# 1-Schematic_CJ4_Electrical_Panel.net
KiCad netlist of a schematic drawn in EasyEDA
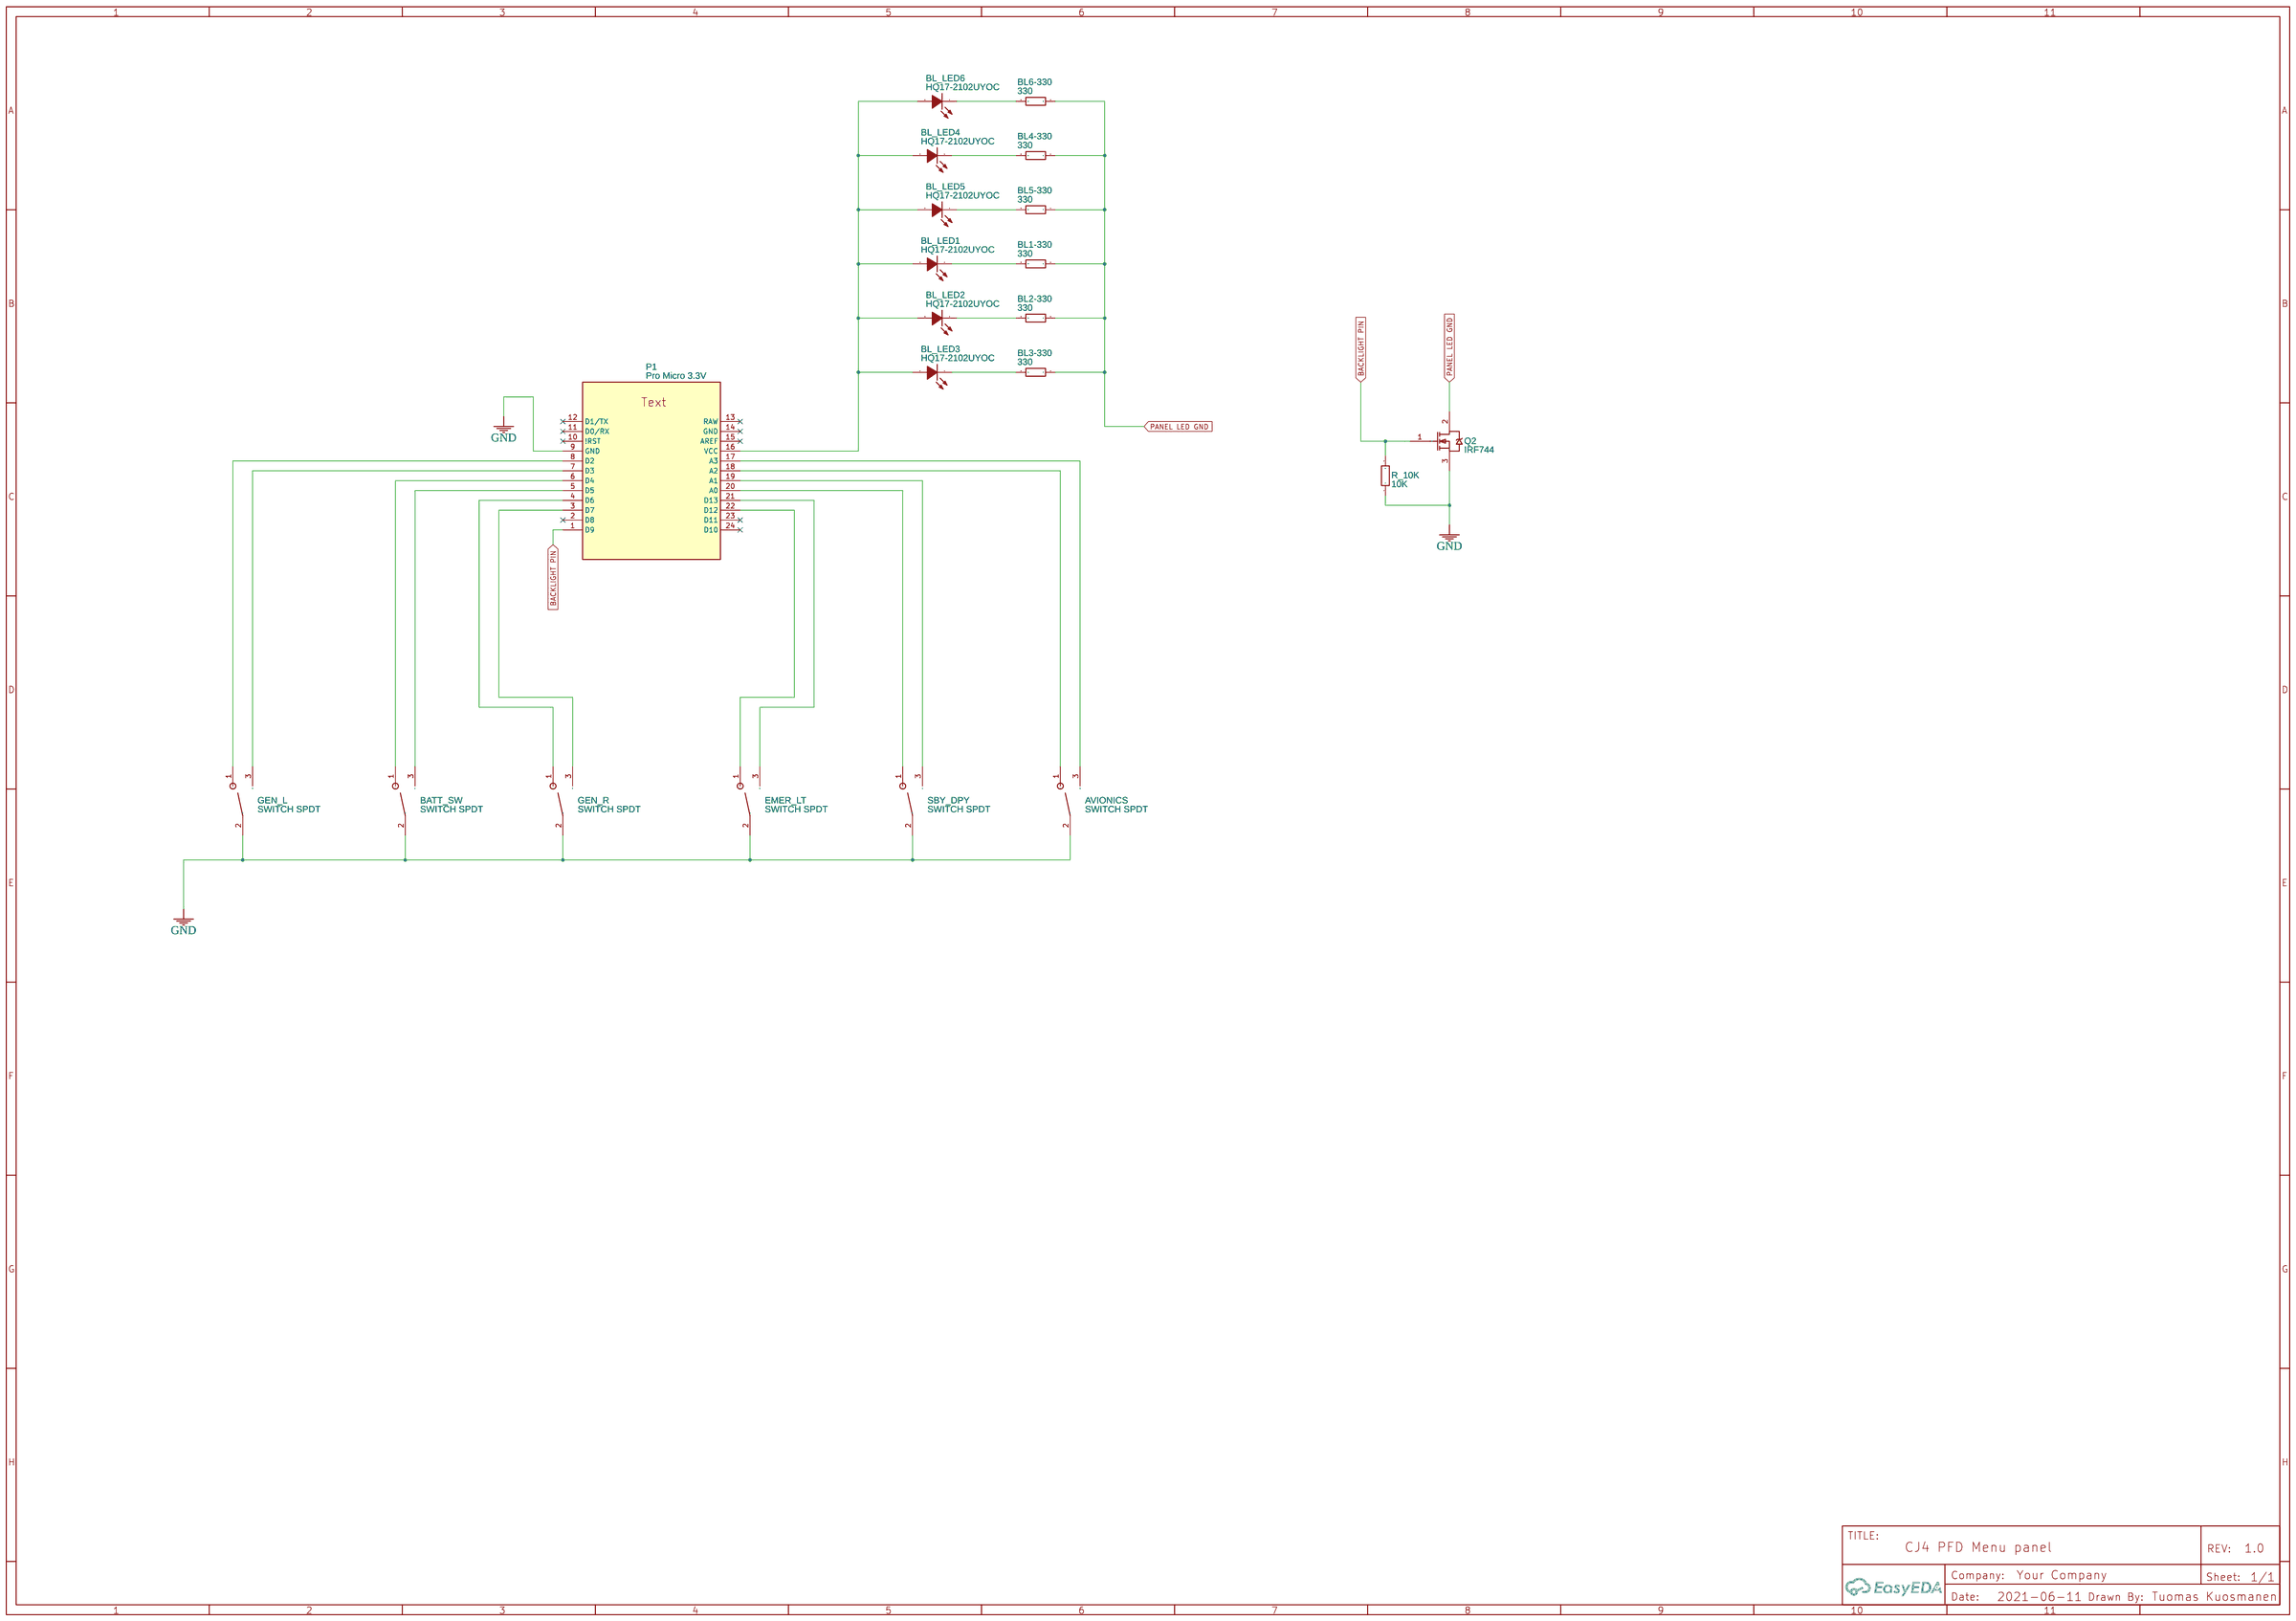
[diagram p0: schematic sheet]

(export (version "E")
  (design (tool "Eeschema 10.0.6"))
  (components
    (comp (ref "AVIONICS")
      (value "SWITCH SPDT")
      (fields
        (field (name "BOM_Manufacturer Part") "200MSP1T1B1M2QEH")
        (field (name "BOM_Supplier Part") "C273365")
      )
      (libsource (lib "") (part "SWITCH SPDT_3"))
    )
    (comp (ref "BATT_SW")
      (value "SWITCH SPDT")
      (fields
        (field (name "BOM_Manufacturer Part") "200MSP1T1B1M2QEH")
        (field (name "BOM_Supplier Part") "C273365")
      )
      (libsource (lib "") (part "SWITCH SPDT_4"))
    )
    (comp (ref "BL1-330")
      (value "330")
      (fields
        (field (name "BOM_Manufacturer Part") "1206W4J0331T5E")
        (field (name "BOM_Supplier Part") "C25374")
      )
      (libsource (lib "") (part "1206W4J0331T5E_3"))
    )
    (comp (ref "BL2-330")
      (value "330")
      (fields
        (field (name "BOM_Manufacturer Part") "1206W4J0331T5E")
        (field (name "BOM_Supplier Part") "C25374")
      )
      (libsource (lib "") (part "1206W4J0331T5E_4"))
    )
    (comp (ref "BL3-330")
      (value "330")
      (fields
        (field (name "BOM_Manufacturer Part") "1206W4J0331T5E")
        (field (name "BOM_Supplier Part") "C25374")
      )
      (libsource (lib "") (part "1206W4J0331T5E_6"))
    )
    (comp (ref "BL4-330")
      (value "330")
      (fields
        (field (name "BOM_Manufacturer Part") "1206W4J0331T5E")
        (field (name "BOM_Supplier Part") "C25374")
      )
      (libsource (lib "") (part "1206W4J0331T5E"))
    )
    (comp (ref "BL5-330")
      (value "330")
      (fields
        (field (name "BOM_Manufacturer Part") "1206W4J0331T5E")
        (field (name "BOM_Supplier Part") "C25374")
      )
      (libsource (lib "") (part "1206W4J0331T5E_1"))
    )
    (comp (ref "BL6-330")
      (value "330")
      (fields
        (field (name "BOM_Manufacturer Part") "1206W4J0331T5E")
        (field (name "BOM_Supplier Part") "C25374")
      )
      (libsource (lib "") (part "1206W4J0331T5E_5"))
    )
    (comp (ref "BL_LED1")
      (value "HQ17-2102UYOC")
      (fields (field (name "BOM_Supplier Part") "C154481"))
      (libsource (lib "") (part "HQ17-2102UYOC"))
    )
    (comp (ref "BL_LED2")
      (value "HQ17-2102UYOC")
      (fields (field (name "BOM_Supplier Part") "C154481"))
      (libsource (lib "") (part "HQ17-2102UYOC"))
    )
    (comp (ref "BL_LED3")
      (value "HQ17-2102UYOC")
      (fields (field (name "BOM_Supplier Part") "C154481"))
      (libsource (lib "") (part "HQ17-2102UYOC"))
    )
    (comp (ref "BL_LED4")
      (value "HQ17-2102UYOC")
      (fields (field (name "BOM_Supplier Part") "C154481"))
      (libsource (lib "") (part "HQ17-2102UYOC"))
    )
    (comp (ref "BL_LED5")
      (value "HQ17-2102UYOC")
      (fields (field (name "BOM_Supplier Part") "C154481"))
      (libsource (lib "") (part "HQ17-2102UYOC"))
    )
    (comp (ref "BL_LED6")
      (value "HQ17-2102UYOC")
      (fields (field (name "BOM_Supplier Part") "C154481"))
      (libsource (lib "") (part "HQ17-2102UYOC"))
    )
    (comp (ref "EMER_LT")
      (value "SWITCH SPDT")
      (fields
        (field (name "BOM_Manufacturer Part") "200MSP1T1B1M2QEH")
        (field (name "BOM_Supplier Part") "C273365")
      )
      (libsource (lib "") (part "SWITCH SPDT_5"))
    )
    (comp (ref "GEN_L")
      (value "SWITCH SPDT")
      (fields
        (field (name "BOM_Manufacturer Part") "200MSP1T1B1M2QEH")
        (field (name "BOM_Supplier Part") "C273365")
      )
      (libsource (lib "") (part "SWITCH SPDT_2"))
    )
    (comp (ref "GEN_R")
      (value "SWITCH SPDT")
      (fields
        (field (name "BOM_Manufacturer Part") "200MSP1T1B1M2QEH")
        (field (name "BOM_Supplier Part") "C273365")
      )
      (libsource (lib "") (part "SWITCH SPDT_1"))
    )
    (comp (ref "P1")
      (value "Pro Micro 3.3V")
      (fields (field (name "BOM_Supplier Part") "12587"))
      (libsource (lib "") (part "Pro Micro 3.3V"))
    )
    (comp (ref "Q2") (value "IRF744") (libsource (lib "") (part "IRF744")))
    (comp (ref "R_10K")
      (value "10K")
      (fields
        (field (name "BOM_Manufacturer Part") "1206W4J0331T5E")
        (field (name "BOM_Supplier Part") "C25374")
      )
      (libsource (lib "") (part "1206W4J0331T5E_2"))
    )
    (comp (ref "SBY_DPY")
      (value "SWITCH SPDT")
      (fields
        (field (name "BOM_Manufacturer Part") "200MSP1T1B1M2QEH")
        (field (name "BOM_Supplier Part") "C273365")
      )
      (libsource (lib "") (part "SWITCH SPDT"))
    )
  )
  (nets
    (net (code "1") (name "BACKLIGHT PIN") (class "Default")
      (node (ref "P1") (pin "1") (pinfunction "D9_1") (pintype "unspecified"))
      (node (ref "Q2") (pin "1") (pinfunction "G_1") (pintype "unspecified"))
      (node (ref "R_10K") (pin "2") (pinfunction "2_2") (pintype "input"))
    )
    (net (code "2") (name "GND") (class "Default")
      (node (ref "AVIONICS") (pin "2") (pinfunction "2_2") (pintype "input"))
      (node (ref "BATT_SW") (pin "2") (pinfunction "2_2") (pintype "input"))
      (node (ref "EMER_LT") (pin "2") (pinfunction "2_2") (pintype "input"))
      (node (ref "GEN_L") (pin "2") (pinfunction "2_2") (pintype "input"))
      (node (ref "GEN_R") (pin "2") (pinfunction "2_2") (pintype "input"))
      (node (ref "P1") (pin "9") (pinfunction "GND_9") (pintype "unspecified"))
      (node (ref "Q2") (pin "3") (pinfunction "S_3") (pintype "unspecified"))
      (node (ref "R_10K") (pin "1") (pinfunction "1_1") (pintype "input"))
      (node (ref "SBY_DPY") (pin "2") (pinfunction "2_2") (pintype "input"))
    )
    (net (code "3") (name "Net-(BL_LED1-A)") (class "Default")
      (node (ref "BL_LED1") (pin "2") (pinfunction "A_2") (pintype "unspecified"))
      (node (ref "BL_LED2") (pin "2") (pinfunction "A_2") (pintype "unspecified"))
      (node (ref "BL_LED3") (pin "2") (pinfunction "A_2") (pintype "unspecified"))
      (node (ref "BL_LED4") (pin "2") (pinfunction "A_2") (pintype "unspecified"))
      (node (ref "BL_LED5") (pin "2") (pinfunction "A_2") (pintype "unspecified"))
      (node (ref "BL_LED6") (pin "2") (pinfunction "A_2") (pintype "unspecified"))
      (node (ref "P1") (pin "16") (pinfunction "VCC_16") (pintype "unspecified"))
    )
    (net (code "4") (name "Net-(BL_LED1-K)") (class "Default")
      (node (ref "BL1-330") (pin "2") (pinfunction "2_2") (pintype "input"))
      (node (ref "BL_LED1") (pin "1") (pinfunction "K_1") (pintype "unspecified"))
    )
    (net (code "5") (name "Net-(BL_LED2-K)") (class "Default")
      (node (ref "BL2-330") (pin "2") (pinfunction "2_2") (pintype "input"))
      (node (ref "BL_LED2") (pin "1") (pinfunction "K_1") (pintype "unspecified"))
    )
    (net (code "6") (name "Net-(BL_LED3-K)") (class "Default")
      (node (ref "BL3-330") (pin "2") (pinfunction "2_2") (pintype "input"))
      (node (ref "BL_LED3") (pin "1") (pinfunction "K_1") (pintype "unspecified"))
    )
    (net (code "7") (name "Net-(BL_LED4-K)") (class "Default")
      (node (ref "BL4-330") (pin "2") (pinfunction "2_2") (pintype "input"))
      (node (ref "BL_LED4") (pin "1") (pinfunction "K_1") (pintype "unspecified"))
    )
    (net (code "8") (name "Net-(BL_LED5-K)") (class "Default")
      (node (ref "BL5-330") (pin "2") (pinfunction "2_2") (pintype "input"))
      (node (ref "BL_LED5") (pin "1") (pinfunction "K_1") (pintype "unspecified"))
    )
    (net (code "9") (name "Net-(BL_LED6-K)") (class "Default")
      (node (ref "BL6-330") (pin "2") (pinfunction "2_2") (pintype "input"))
      (node (ref "BL_LED6") (pin "1") (pinfunction "K_1") (pintype "unspecified"))
    )
    (net (code "10") (name "Net-(P1-A0)") (class "Default")
      (node (ref "P1") (pin "20") (pinfunction "A0_20") (pintype "unspecified"))
      (node (ref "SBY_DPY") (pin "1") (pinfunction "1_1") (pintype "input"))
    )
    (net (code "11") (name "Net-(P1-A1)") (class "Default")
      (node (ref "P1") (pin "19") (pinfunction "A1_19") (pintype "unspecified"))
      (node (ref "SBY_DPY") (pin "3") (pinfunction "3_3") (pintype "input"))
    )
    (net (code "12") (name "Net-(P1-A2)") (class "Default")
      (node (ref "AVIONICS") (pin "1") (pinfunction "1_1") (pintype "input"))
      (node (ref "P1") (pin "18") (pinfunction "A2_18") (pintype "unspecified"))
    )
    (net (code "13") (name "Net-(P1-A3)") (class "Default")
      (node (ref "AVIONICS") (pin "3") (pinfunction "3_3") (pintype "input"))
      (node (ref "P1") (pin "17") (pinfunction "A3_17") (pintype "unspecified"))
    )
    (net (code "14") (name "Net-(P1-D2)") (class "Default")
      (node (ref "GEN_L") (pin "1") (pinfunction "1_1") (pintype "input"))
      (node (ref "P1") (pin "8") (pinfunction "D2_8") (pintype "unspecified"))
    )
    (net (code "15") (name "Net-(P1-D3)") (class "Default")
      (node (ref "GEN_L") (pin "3") (pinfunction "3_3") (pintype "input"))
      (node (ref "P1") (pin "7") (pinfunction "D3_7") (pintype "unspecified"))
    )
    (net (code "16") (name "Net-(P1-D4)") (class "Default")
      (node (ref "BATT_SW") (pin "1") (pinfunction "1_1") (pintype "input"))
      (node (ref "P1") (pin "6") (pinfunction "D4_6") (pintype "unspecified"))
    )
    (net (code "17") (name "Net-(P1-D5)") (class "Default")
      (node (ref "BATT_SW") (pin "3") (pinfunction "3_3") (pintype "input"))
      (node (ref "P1") (pin "5") (pinfunction "D5_5") (pintype "unspecified"))
    )
    (net (code "18") (name "Net-(P1-D6)") (class "Default")
      (node (ref "GEN_R") (pin "1") (pinfunction "1_1") (pintype "input"))
      (node (ref "P1") (pin "4") (pinfunction "D6_4") (pintype "unspecified"))
    )
    (net (code "19") (name "Net-(P1-D7)") (class "Default")
      (node (ref "GEN_R") (pin "3") (pinfunction "3_3") (pintype "input"))
      (node (ref "P1") (pin "3") (pinfunction "D7_3") (pintype "unspecified"))
    )
    (net (code "20") (name "Net-(P1-D12)") (class "Default")
      (node (ref "EMER_LT") (pin "1") (pinfunction "1_1") (pintype "input"))
      (node (ref "P1") (pin "22") (pinfunction "D12_22") (pintype "unspecified"))
    )
    (net (code "21") (name "Net-(P1-D13)") (class "Default")
      (node (ref "EMER_LT") (pin "3") (pinfunction "3_3") (pintype "input"))
      (node (ref "P1") (pin "21") (pinfunction "D13_21") (pintype "unspecified"))
    )
    (net (code "22") (name "PANEL LED GND") (class "Default")
      (node (ref "BL1-330") (pin "1") (pinfunction "1_1") (pintype "input"))
      (node (ref "BL2-330") (pin "1") (pinfunction "1_1") (pintype "input"))
      (node (ref "BL3-330") (pin "1") (pinfunction "1_1") (pintype "input"))
      (node (ref "BL4-330") (pin "1") (pinfunction "1_1") (pintype "input"))
      (node (ref "BL5-330") (pin "1") (pinfunction "1_1") (pintype "input"))
      (node (ref "BL6-330") (pin "1") (pinfunction "1_1") (pintype "input"))
      (node (ref "Q2") (pin "2") (pinfunction "D_2") (pintype "unspecified"))
    )
    (net (code "23") (name "unconnected-(P1-!RST-Pad10)") (class "Default")
      (node (ref "P1") (pin "10") (pinfunction "!RST_10") (pintype "unspecified+no_connect"))
    )
    (net (code "24") (name "unconnected-(P1-AREF-Pad15)") (class "Default")
      (node (ref "P1") (pin "15") (pinfunction "AREF_15") (pintype "unspecified+no_connect"))
    )
    (net (code "25") (name "unconnected-(P1-D0{slash}RX-Pad11)") (class "Default")
      (node (ref "P1") (pin "11") (pinfunction "D0/RX_11") (pintype "unspecified+no_connect"))
    )
    (net (code "26") (name "unconnected-(P1-D1{slash}TX-Pad12)") (class "Default")
      (node (ref "P1") (pin "12") (pinfunction "D1/TX_12") (pintype "unspecified+no_connect"))
    )
    (net (code "27") (name "unconnected-(P1-D8-Pad2)") (class "Default")
      (node (ref "P1") (pin "2") (pinfunction "D8_2") (pintype "unspecified+no_connect"))
    )
    (net (code "28") (name "unconnected-(P1-D10-Pad24)") (class "Default")
      (node (ref "P1") (pin "24") (pinfunction "D10_24") (pintype "unspecified+no_connect"))
    )
    (net (code "29") (name "unconnected-(P1-D11-Pad23)") (class "Default")
      (node (ref "P1") (pin "23") (pinfunction "D11_23") (pintype "unspecified+no_connect"))
    )
    (net (code "30") (name "unconnected-(P1-GND-Pad14)") (class "Default")
      (node (ref "P1") (pin "14") (pinfunction "GND_14") (pintype "unspecified+no_connect"))
    )
    (net (code "31") (name "unconnected-(P1-RAW-Pad13)") (class "Default")
      (node (ref "P1") (pin "13") (pinfunction "RAW_13") (pintype "unspecified+no_connect"))
    )
  )
)
